# PWR_MGMT.net
KiCad netlist of a schematic drawn in Altium Designer
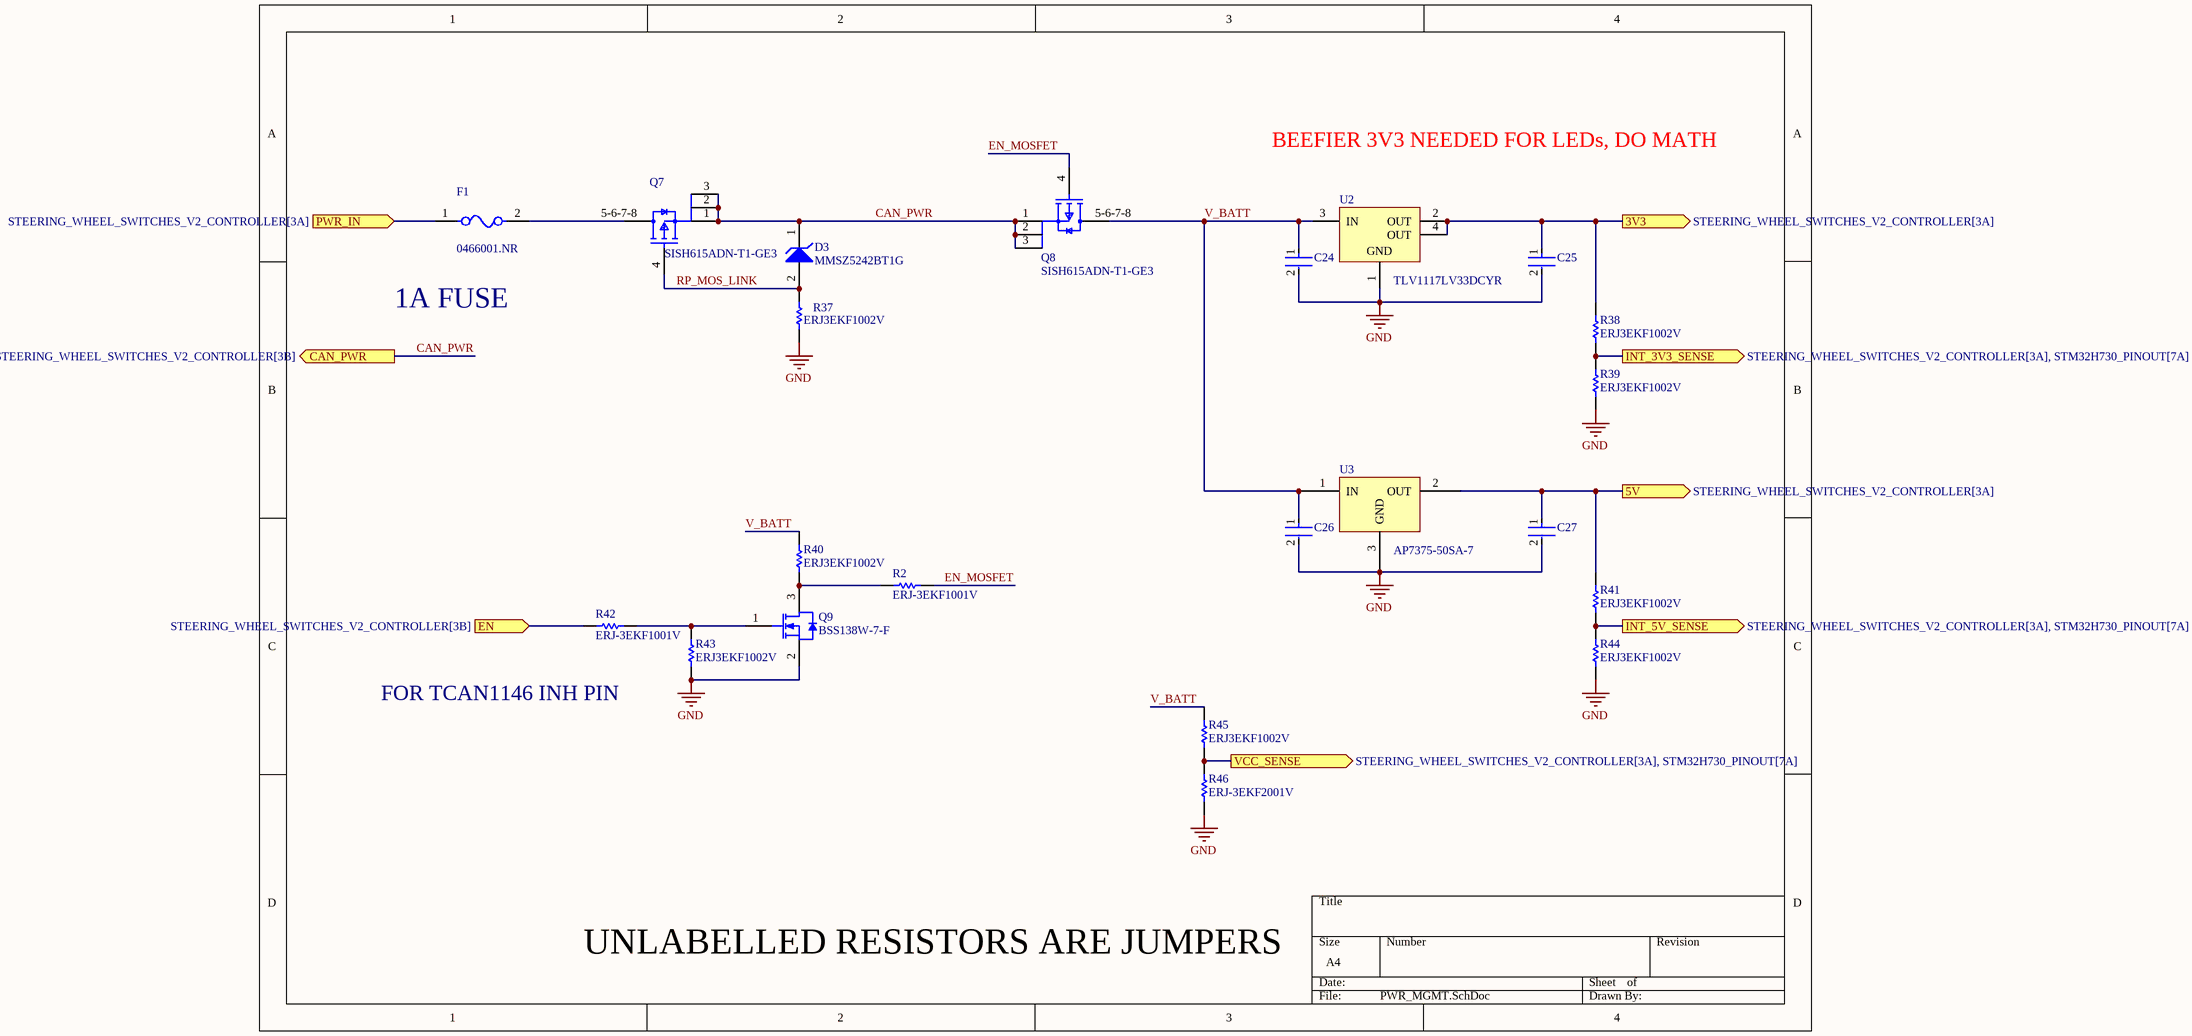
[diagram p0: PWR_MGMT.SchDoc]

(export (version "E")
  (design (tool "Eeschema 10.0.6"))
  (components
    (comp (ref "C24")
      (value "GRM188R61E106KA73D")
      (footprint "FP-GRM188-0_2-IPC_A")
      (description "Chip Multilayer Ceramic Capacitors for General Purpose, 0603, 10uF, X5R, 15%, 10%, 25V")
      (libsource (lib "Altium Content Vault") (part "11868f565c42a9108669ba33697ecf6"))
    )
    (comp (ref "C25")
      (value "GRM188R61E106KA73D")
      (footprint "FP-GRM188-0_2-IPC_A")
      (description "Chip Multilayer Ceramic Capacitors for General Purpose, 0603, 10uF, X5R, 15%, 10%, 25V")
      (libsource (lib "Altium Content Vault") (part "11868f565c42a9108669ba33697ecf6"))
    )
    (comp (ref "C26")
      (value "GRM188R61E106KA73D")
      (footprint "FP-GRM188-0_2-IPC_A")
      (description "Chip Multilayer Ceramic Capacitors for General Purpose, 0603, 10uF, X5R, 15%, 10%, 25V")
      (libsource (lib "Altium Content Vault") (part "11868f565c42a9108669ba33697ecf6"))
    )
    (comp (ref "C27")
      (value "GRM188R61E106KA73D")
      (footprint "FP-GRM188-0_2-IPC_A")
      (description "Chip Multilayer Ceramic Capacitors for General Purpose, 0603, 10uF, X5R, 15%, 10%, 25V")
      (libsource (lib "Altium Content Vault") (part "11868f565c42a9108669ba33697ecf6"))
    )
    (comp (ref "D3")
      (value "MMSZ5242BT1G")
      (footprint "ONSC-SOD-123-2-425-04_V")
      (description "Zener Voltage Regulator, 500 mW, 2-Pin SOD-123, Pb-Free, Tape and Reel")
      (fields (field (name "MANUFACTURER") "On Semiconductor"))
      (libsource (lib "Altium Content Vault") (part "ONSC-K1A2-2"))
    )
    (comp (ref "F1")
      (value "0466001.NR")
      (footprint "FP-0466-MFG")
      (description "FUSE BOARD MNT 1A 63VAC/VDC 1206")
      (fields
        (field (name "MANUFACTURER") "Littelfuse Inc")
        (field (name "OCTOPART") "https://octopart.com/0466001.nr-littelfuse-566005")
      )
      (libsource (lib "Altium Content Vault") (part "5bcf9b9f640e542cf0359d10258e979"))
    )
    (comp (ref "Q7")
      (value "SISH615ADN-T1-GE3")
      (footprint "SISH615ADN-T1-GE3-Footprint-1")
      (description "Trans MOSFET P-CH 20V 22.1A 8-Pin PowerPAK 1212 EP T/R")
      (libsource (lib "Space Concordia") (part "CMP-013-00036-4"))
    )
    (comp (ref "Q8")
      (value "SISH615ADN-T1-GE3")
      (footprint "SISH615ADN-T1-GE3-Footprint-1")
      (description "Trans MOSFET P-CH 20V 22.1A 8-Pin PowerPAK 1212 EP T/R")
      (libsource (lib "Space Concordia") (part "CMP-013-00036-4"))
    )
    (comp (ref "Q9")
      (value "BSS138W-7-F")
      (footprint "DIOD-SOT323-3_V")
      (fields (field (name "MANUFACTURER") "DiodesIncorporated"))
      (libsource (lib "Altium Content Vault") (part "NEMOS-GSD-3"))
    )
    (comp (ref "R2")
      (value "ERJ-3EKF1001V")
      (footprint "RESC1608X55X30LL15T15")
      (fields (field (name "MANUFACTURER") "Panasonic"))
      (libsource (lib "Altium Content Vault") (part "RES"))
    )
    (comp (ref "R37")
      (value "ERJ3EKF1002V")
      (footprint "RESC1609X55X30LL15T15")
      (description "Chip Resistor, 10 KOhm, +/- 1%, 0.1 W, -55 to 155 degC, 0603 (1608 Metric), RoHS, Tape and Reel")
      (fields (field (name "TOLERANCE") "1%") (field (name "MANUFACTURER") "Panasonic"))
      (libsource (lib "Altium Content Vault") (part "RES-2"))
    )
    (comp (ref "R38")
      (value "ERJ3EKF1002V")
      (footprint "RESC1609X55X30LL15T15")
      (description "Chip Resistor, 10 KOhm, +/- 1%, 0.1 W, -55 to 155 degC, 0603 (1608 Metric), RoHS, Tape and Reel")
      (fields (field (name "TOLERANCE") "1%") (field (name "MANUFACTURER") "Panasonic"))
      (libsource (lib "Altium Content Vault") (part "RES-2"))
    )
    (comp (ref "R39")
      (value "ERJ3EKF1002V")
      (footprint "RESC1609X55X30LL15T15")
      (description "Chip Resistor, 10 KOhm, +/- 1%, 0.1 W, -55 to 155 degC, 0603 (1608 Metric), RoHS, Tape and Reel")
      (fields (field (name "TOLERANCE") "1%") (field (name "MANUFACTURER") "Panasonic"))
      (libsource (lib "Altium Content Vault") (part "RES-2"))
    )
    (comp (ref "R40")
      (value "ERJ3EKF1002V")
      (footprint "RESC1609X55X30LL15T15")
      (description "Chip Resistor, 10 KOhm, +/- 1%, 0.1 W, -55 to 155 degC, 0603 (1608 Metric), RoHS, Tape and Reel")
      (fields (field (name "TOLERANCE") "1%") (field (name "MANUFACTURER") "Panasonic"))
      (libsource (lib "Altium Content Vault") (part "RES-2"))
    )
    (comp (ref "R41")
      (value "ERJ3EKF1002V")
      (footprint "RESC1609X55X30LL15T15")
      (description "Chip Resistor, 10 KOhm, +/- 1%, 0.1 W, -55 to 155 degC, 0603 (1608 Metric), RoHS, Tape and Reel")
      (fields (field (name "TOLERANCE") "1%") (field (name "MANUFACTURER") "Panasonic"))
      (libsource (lib "Altium Content Vault") (part "RES-2"))
    )
    (comp (ref "R42")
      (value "ERJ-3EKF1001V")
      (footprint "RESC1608X55X30LL15T15")
      (fields (field (name "MANUFACTURER") "Panasonic"))
      (libsource (lib "Altium Content Vault") (part "RES"))
    )
    (comp (ref "R43")
      (value "ERJ3EKF1002V")
      (footprint "RESC1609X55X30LL15T15")
      (description "Chip Resistor, 10 KOhm, +/- 1%, 0.1 W, -55 to 155 degC, 0603 (1608 Metric), RoHS, Tape and Reel")
      (fields (field (name "TOLERANCE") "1%") (field (name "MANUFACTURER") "Panasonic"))
      (libsource (lib "Altium Content Vault") (part "RES-2"))
    )
    (comp (ref "R44")
      (value "ERJ3EKF1002V")
      (footprint "RESC1609X55X30LL15T15")
      (description "Chip Resistor, 10 KOhm, +/- 1%, 0.1 W, -55 to 155 degC, 0603 (1608 Metric), RoHS, Tape and Reel")
      (fields (field (name "TOLERANCE") "1%") (field (name "MANUFACTURER") "Panasonic"))
      (libsource (lib "Altium Content Vault") (part "RES-2"))
    )
    (comp (ref "R45")
      (value "ERJ3EKF1002V")
      (footprint "RESC1609X55X30LL15T15")
      (description "Chip Resistor, 10 KOhm, +/- 1%, 0.1 W, -55 to 155 degC, 0603 (1608 Metric), RoHS, Tape and Reel")
      (fields (field (name "TOLERANCE") "1%") (field (name "MANUFACTURER") "Panasonic"))
      (libsource (lib "Altium Content Vault") (part "RES-2"))
    )
    (comp (ref "R46")
      (value "ERJ-3EKF2001V")
      (footprint "RESC1608X55X30ML15T15")
      (fields (field (name "MANUFACTURER") "Panasonic"))
      (libsource (lib "Altium Content Vault") (part "RES"))
    )
    (comp (ref "U2")
      (value "TLV1117LV33DCYR")
      (footprint "DCY0004A_N")
      (fields (field (name "MANUFACTURER") "Texas Instruments"))
      (libsource (lib "Altium Content Vault") (part "TI-TLV1117LV33DCY4"))
    )
    (comp (ref "U3")
      (value "AP7375-50SA-7")
      (footprint "AP7375-50SA-7-Footprint-1")
      (description "Ldo Cmos Lowcurr SOT23 T&r 3K")
      (libsource (lib "Space Concordia") (part "AP7375-50SA-7"))
    )
  )
  (nets
    (net (code "1") (name "/3V3") (class "Default")
      (node (ref "C25") (pin "1") (pinfunction "1_1") (pintype "passive"))
      (node (ref "R38") (pin "2") (pinfunction "2_2") (pintype "passive"))
      (node (ref "U2") (pin "2") (pinfunction "OUT_2") (pintype "power_in"))
      (node (ref "U2") (pin "4") (pinfunction "OUT_4") (pintype "power_in"))
    )
    (net (code "2") (name "/5V") (class "Default")
      (node (ref "C27") (pin "1") (pinfunction "1_1") (pintype "passive"))
      (node (ref "R41") (pin "2") (pinfunction "2_2") (pintype "passive"))
      (node (ref "U3") (pin "2") (pinfunction "OUT_2") (pintype "passive"))
    )
    (net (code "3") (name "/CAN_PWR") (class "Default")
      (node (ref "D3") (pin "1") (pinfunction "K_1") (pintype "passive"))
      (node (ref "Q7") (pin "1") (pinfunction "S_1") (pintype "passive"))
      (node (ref "Q7") (pin "2") (pinfunction "S_2") (pintype "passive"))
      (node (ref "Q7") (pin "3") (pinfunction "S_3") (pintype "passive"))
      (node (ref "Q8") (pin "1") (pinfunction "S_1") (pintype "passive"))
      (node (ref "Q8") (pin "2") (pinfunction "S_2") (pintype "passive"))
      (node (ref "Q8") (pin "3") (pinfunction "S_3") (pintype "passive"))
    )
    (net (code "4") (name "/EN") (class "Default")
      (node (ref "R42") (pin "2") (pinfunction "2_2") (pintype "passive"))
    )
    (net (code "5") (name "/EN_MOSFET") (class "Default")
      (node (ref "Q8") (pin "4") (pinfunction "G_4") (pintype "passive"))
      (node (ref "R2") (pin "1") (pinfunction "1_1") (pintype "passive"))
    )
    (net (code "6") (name "/INT_3V3_SENSE") (class "Default")
      (node (ref "R38") (pin "1") (pinfunction "1_1") (pintype "passive"))
      (node (ref "R39") (pin "2") (pinfunction "2_2") (pintype "passive"))
    )
    (net (code "7") (name "/INT_5V_SENSE") (class "Default")
      (node (ref "R41") (pin "1") (pinfunction "1_1") (pintype "passive"))
      (node (ref "R44") (pin "1") (pinfunction "1_1") (pintype "passive"))
    )
    (net (code "8") (name "/PWR_IN") (class "Default")
      (node (ref "F1") (pin "1") (pinfunction "1_1") (pintype "passive"))
    )
    (net (code "9") (name "/RP_MOS_LINK") (class "Default")
      (node (ref "D3") (pin "2") (pinfunction "A_2") (pintype "passive"))
      (node (ref "Q7") (pin "4") (pinfunction "G_4") (pintype "passive"))
      (node (ref "R37") (pin "1") (pinfunction "1_1") (pintype "passive"))
    )
    (net (code "10") (name "/VCC_SENSE") (class "Default")
      (node (ref "R45") (pin "1") (pinfunction "1_1") (pintype "passive"))
      (node (ref "R46") (pin "2") (pinfunction "2_2") (pintype "passive"))
    )
    (net (code "11") (name "/V_BATT") (class "Default")
      (node (ref "C24") (pin "1") (pinfunction "1_1") (pintype "passive"))
      (node (ref "C26") (pin "1") (pinfunction "1_1") (pintype "passive"))
      (node (ref "Q8") (pin "5-6-7-8") (pinfunction "D_5-6-7-8") (pintype "passive"))
      (node (ref "R40") (pin "2") (pinfunction "2_2") (pintype "passive"))
      (node (ref "R45") (pin "2") (pinfunction "2_2") (pintype "passive"))
      (node (ref "U2") (pin "3") (pinfunction "IN_3") (pintype "power_in"))
      (node (ref "U3") (pin "1") (pinfunction "IN_1") (pintype "passive"))
    )
    (net (code "12") (name "GND") (class "Default")
      (node (ref "C24") (pin "2") (pinfunction "2_2") (pintype "passive"))
      (node (ref "C25") (pin "2") (pinfunction "2_2") (pintype "passive"))
      (node (ref "C26") (pin "2") (pinfunction "2_2") (pintype "passive"))
      (node (ref "C27") (pin "2") (pinfunction "2_2") (pintype "passive"))
      (node (ref "Q9") (pin "2") (pinfunction "S_2") (pintype "passive"))
      (node (ref "R37") (pin "2") (pinfunction "2_2") (pintype "passive"))
      (node (ref "R39") (pin "1") (pinfunction "1_1") (pintype "passive"))
      (node (ref "R43") (pin "1") (pinfunction "1_1") (pintype "passive"))
      (node (ref "R44") (pin "2") (pinfunction "2_2") (pintype "passive"))
      (node (ref "R46") (pin "1") (pinfunction "1_1") (pintype "passive"))
      (node (ref "U2") (pin "1") (pinfunction "GND_1") (pintype "power_in"))
      (node (ref "U3") (pin "3") (pinfunction "GND_3") (pintype "passive"))
    )
    (net (code "13") (name "Net-(Q7-D)") (class "Default")
      (node (ref "F1") (pin "2") (pinfunction "2_2") (pintype "passive"))
      (node (ref "Q7") (pin "5-6-7-8") (pinfunction "D_5-6-7-8") (pintype "passive"))
    )
    (net (code "14") (name "Net-(Q9-D)") (class "Default")
      (node (ref "Q9") (pin "3") (pinfunction "D_3") (pintype "passive"))
      (node (ref "R2") (pin "2") (pinfunction "2_2") (pintype "passive"))
      (node (ref "R40") (pin "1") (pinfunction "1_1") (pintype "passive"))
    )
    (net (code "15") (name "Net-(Q9-G)") (class "Default")
      (node (ref "Q9") (pin "1") (pinfunction "G_1") (pintype "passive"))
      (node (ref "R42") (pin "1") (pinfunction "1_1") (pintype "passive"))
      (node (ref "R43") (pin "2") (pinfunction "2_2") (pintype "passive"))
    )
  )
)
